# RetroLink.net
KiCad netlist of a schematic drawn in EAGLE
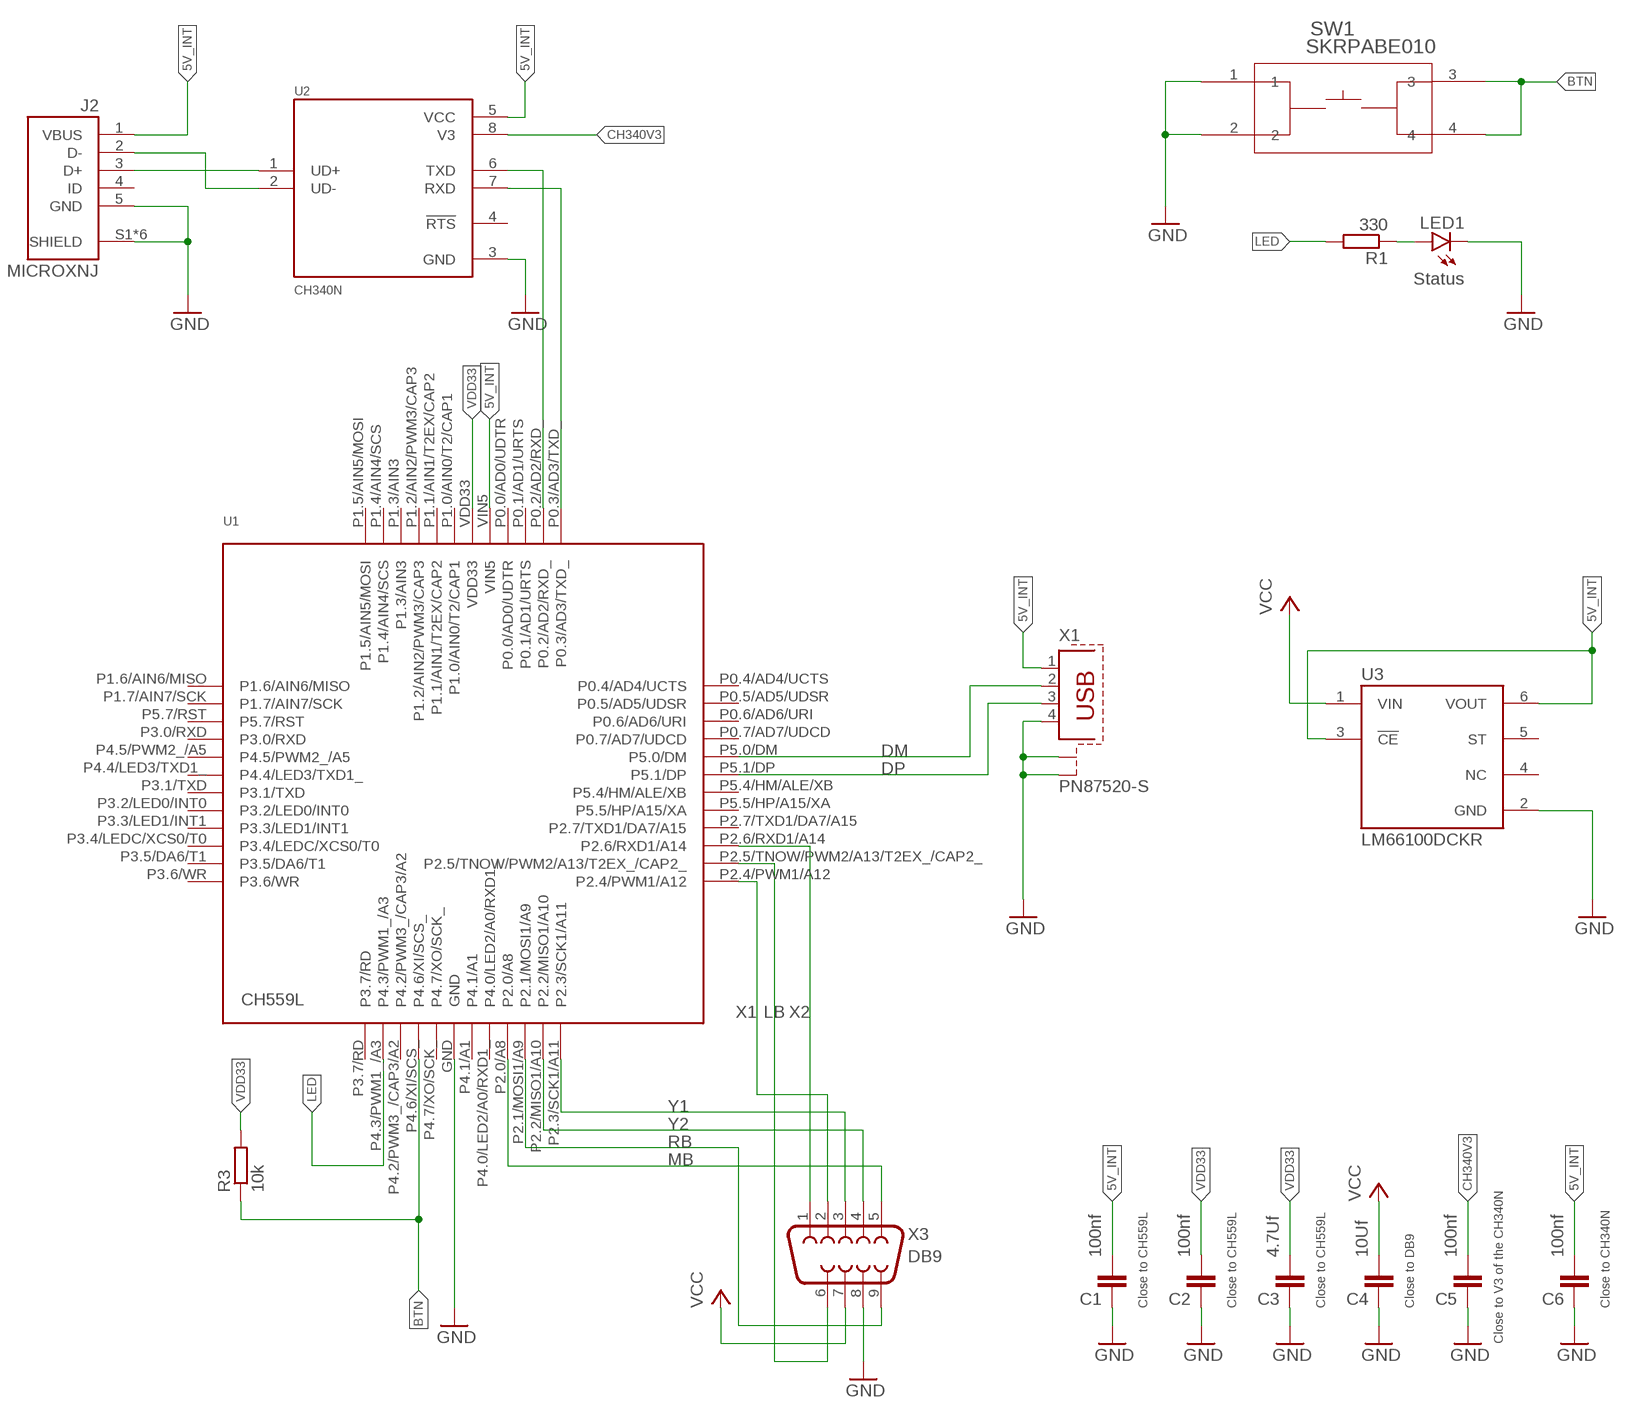
[diagram p0: schematic, sheet 1]

(export (version "E")
  (design (tool "Eeschema 10.0.6"))
  (components
    (comp (ref "C1")
      (value "100nf")
      (footprint "eagle-import:C0603")
      (libsource (lib "eagle-import") (part "C-EUC0603"))
    )
    (comp (ref "C2")
      (value "100nf")
      (footprint "eagle-import:C0603")
      (libsource (lib "eagle-import") (part "C-EUC0603"))
    )
    (comp (ref "C3")
      (value "4.7Uf")
      (footprint "eagle-import:C0603")
      (libsource (lib "eagle-import") (part "C-EUC0603"))
    )
    (comp (ref "C4")
      (value "10Uf")
      (footprint "eagle-import:C0603")
      (libsource (lib "eagle-import") (part "C-EUC0603"))
    )
    (comp (ref "C5")
      (value "100nf")
      (footprint "eagle-import:C0603")
      (libsource (lib "eagle-import") (part "C-EUC0603"))
    )
    (comp (ref "C6")
      (value "100nf")
      (footprint "eagle-import:C0603")
      (libsource (lib "eagle-import") (part "C-EUC0603"))
    )
    (comp (ref "J2")
      (value "MICROXNJ")
      (footprint "eagle-import:SHOUHAN_MICROXNJ")
      (fields (field (name "MF") "Shouhan"))
      (libsource (lib "eagle-import") (part "MICROXNJ"))
    )
    (comp (ref "LED1")
      (value "Status")
      (footprint "eagle-import:SML0603")
      (libsource (lib "eagle-import") (part "LEDSML0603"))
    )
    (comp (ref "R1")
      (value "330")
      (footprint "eagle-import:R0603")
      (libsource (lib "eagle-import") (part "R-EU_R0603"))
    )
    (comp (ref "R3")
      (value "10k")
      (footprint "eagle-import:R0603")
      (libsource (lib "eagle-import") (part "R-EU_R0603"))
    )
    (comp (ref "SW1")
      (value "SKRPABE010")
      (footprint "eagle-import:SW4_SKRPABE010_ALPS")
      (fields (field (name "COPYRIGHT") "Copyright (C) 2026 Ultra Librarian. All rights reserved."))
      (libsource (lib "eagle-import") (part "SKRPABE010"))
    )
    (comp (ref "U1")
      (value "CH559L")
      (footprint "eagle-import:TQFP48_7X7")
      (libsource (lib "eagle-import") (part "CH559L"))
    )
    (comp (ref "U2")
      (value "CH340N")
      (footprint "eagle-import:SOIC127P600X160-8N")
      (fields (field (name "MF") "WCH"))
      (libsource (lib "eagle-import") (part "CH340N"))
    )
    (comp (ref "U3")
      (value "LM66100DCKR")
      (footprint "eagle-import:SOT65P210X110-6N")
      (fields (field (name "MF") "Texas Instruments"))
      (libsource (lib "eagle-import") (part "LM66100DCKR"))
    )
    (comp (ref "X1")
      (value "PN87520-S")
      (footprint "eagle-import:PN87520-S")
      (libsource (lib "eagle-import") (part "PN87520-S"))
    )
    (comp (ref "X3")
      (value "DB9")
      (footprint "eagle-import:F09D")
      (libsource (lib "eagle-import") (part "F09D"))
    )
  )
  (nets
    (net (code "1") (name "/DM") (class "Default")
      (node (ref "U1") (pin "P5.0/DM") (pinfunction "P5.0/DM_P5.0/DM") (pintype "bidirectional"))
      (node (ref "X1") (pin "2") (pinfunction "2_2") (pintype "passive"))
    )
    (net (code "2") (name "/DP") (class "Default")
      (node (ref "U1") (pin "P5.1/DP") (pinfunction "P5.1/DP_P5.1/DP") (pintype "bidirectional"))
      (node (ref "X1") (pin "3") (pinfunction "3_3") (pintype "passive"))
    )
    (net (code "3") (name "/LB") (class "Default")
      (node (ref "U1") (pin "P2.5/TNOW/PWM2/A13/T2EX_/CAP2_") (pinfunction "P2.5/TNOW/PWM2/A13/T2EX_/CAP2__P2.5/TNOW/PWM2/A13/T2EX_/CAP2_") (pintype "bidirectional"))
      (node (ref "X3") (pin "6") (pinfunction "6_6") (pintype "passive"))
    )
    (net (code "4") (name "/MB") (class "Default")
      (node (ref "U1") (pin "P2.0/A8") (pinfunction "P2.0/A8_P2.0/A8") (pintype "bidirectional"))
      (node (ref "X3") (pin "5") (pinfunction "5_5") (pintype "passive"))
    )
    (net (code "5") (name "/RB") (class "Default")
      (node (ref "U1") (pin "P2.1/MOSI1/A9") (pinfunction "P2.1/MOSI1/A9_P2.1/MOSI1/A9") (pintype "bidirectional"))
      (node (ref "X3") (pin "9") (pinfunction "9_9") (pintype "passive"))
    )
    (net (code "6") (name "/X1") (class "Default")
      (node (ref "U1") (pin "P2.4/PWM1/A12") (pinfunction "P2.4/PWM1/A12_P2.4/PWM1/A12") (pintype "bidirectional"))
      (node (ref "X3") (pin "2") (pinfunction "2_2") (pintype "passive"))
    )
    (net (code "7") (name "/X2") (class "Default")
      (node (ref "U1") (pin "P2.6/RXD1/A14") (pinfunction "P2.6/RXD1/A14_P2.6/RXD1/A14") (pintype "bidirectional"))
      (node (ref "X3") (pin "1") (pinfunction "1_1") (pintype "passive"))
    )
    (net (code "8") (name "/Y1") (class "Default")
      (node (ref "U1") (pin "P2.3/SCK1/A11") (pinfunction "P2.3/SCK1/A11_P2.3/SCK1/A11") (pintype "bidirectional"))
      (node (ref "X3") (pin "3") (pinfunction "3_3") (pintype "passive"))
    )
    (net (code "9") (name "/Y2") (class "Default")
      (node (ref "U1") (pin "P2.2/MISO1/A10") (pinfunction "P2.2/MISO1/A10_P2.2/MISO1/A10") (pintype "bidirectional"))
      (node (ref "X3") (pin "4") (pinfunction "4_4") (pintype "passive"))
    )
    (net (code "10") (name "5V_INT") (class "Default")
      (node (ref "C1") (pin "2") (pinfunction "2_2") (pintype "passive"))
      (node (ref "C6") (pin "2") (pinfunction "2_2") (pintype "passive"))
      (node (ref "J2") (pin "1") (pinfunction "VBUS_1") (pintype "power_in"))
      (node (ref "U1") (pin "VIN5") (pinfunction "VIN5_VIN5") (pintype "bidirectional"))
      (node (ref "U2") (pin "5") (pinfunction "VCC_5") (pintype "power_in"))
      (node (ref "U3") (pin "3") (pinfunction "~{CE}_3") (pintype "input"))
      (node (ref "U3") (pin "6") (pinfunction "VOUT_6") (pintype "output"))
      (node (ref "X1") (pin "1") (pinfunction "1_1") (pintype "passive"))
    )
    (net (code "11") (name "BTN") (class "Default")
      (node (ref "R3") (pin "1") (pinfunction "1_1") (pintype "passive"))
      (node (ref "SW1") (pin "3") (pinfunction "3_3") (pintype "passive"))
      (node (ref "SW1") (pin "4") (pinfunction "4_4") (pintype "passive"))
      (node (ref "U1") (pin "P4.6/XI/SCS_") (pinfunction "P4.6/XI/SCS__P4.6/XI/SCS_") (pintype "bidirectional"))
    )
    (net (code "12") (name "CH340V3") (class "Default")
      (node (ref "C5") (pin "2") (pinfunction "2_2") (pintype "passive"))
      (node (ref "U2") (pin "8") (pinfunction "V3_8") (pintype "power_in"))
    )
    (net (code "13") (name "GND") (class "Default")
      (node (ref "C1") (pin "1") (pinfunction "1_1") (pintype "passive"))
      (node (ref "C2") (pin "1") (pinfunction "1_1") (pintype "passive"))
      (node (ref "C3") (pin "1") (pinfunction "1_1") (pintype "passive"))
      (node (ref "C4") (pin "1") (pinfunction "1_1") (pintype "passive"))
      (node (ref "C5") (pin "1") (pinfunction "1_1") (pintype "passive"))
      (node (ref "C6") (pin "1") (pinfunction "1_1") (pintype "passive"))
      (node (ref "J2") (pin "5") (pinfunction "GND_5") (pintype "power_in"))
      (node (ref "J2") (pin "S1") (pinfunction "SHIELD_S1") (pintype "passive"))
      (node (ref "J2") (pin "S2") (pinfunction "SHIELD_S2") (pintype "passive"))
      (node (ref "J2") (pin "S3") (pinfunction "SHIELD_S3") (pintype "passive"))
      (node (ref "J2") (pin "S4") (pinfunction "SHIELD_S4") (pintype "passive"))
      (node (ref "J2") (pin "S5") (pinfunction "SHIELD_S5") (pintype "passive"))
      (node (ref "J2") (pin "S6") (pinfunction "SHIELD_S6") (pintype "passive"))
      (node (ref "LED1") (pin "C") (pinfunction "C_C") (pintype "passive"))
      (node (ref "SW1") (pin "1") (pinfunction "1_1") (pintype "passive"))
      (node (ref "SW1") (pin "2") (pinfunction "2_2") (pintype "passive"))
      (node (ref "U1") (pin "GND") (pinfunction "GND_GND") (pintype "bidirectional"))
      (node (ref "U2") (pin "3") (pinfunction "GND_3") (pintype "power_in"))
      (node (ref "U3") (pin "2") (pinfunction "GND_2") (pintype "power_in"))
      (node (ref "X1") (pin "4") (pinfunction "4_4") (pintype "passive"))
      (node (ref "X1") (pin "S1") (pinfunction "S1_S1") (pintype "passive"))
      (node (ref "X1") (pin "S2") (pinfunction "S2_S2") (pintype "passive"))
      (node (ref "X3") (pin "8") (pinfunction "8_8") (pintype "passive"))
    )
    (net (code "14") (name "LED") (class "Default")
      (node (ref "R1") (pin "2") (pinfunction "2_2") (pintype "passive"))
      (node (ref "U1") (pin "P4.3/PWM1_/A3") (pinfunction "P4.3/PWM1_/A3_P4.3/PWM1_/A3") (pintype "bidirectional"))
    )
    (net (code "15") (name "Net-(J2-D+)") (class "Default")
      (node (ref "J2") (pin "3") (pinfunction "D+_3") (pintype "bidirectional"))
      (node (ref "U2") (pin "1") (pinfunction "UD+_1") (pintype "bidirectional"))
    )
    (net (code "16") (name "Net-(J2-D-)") (class "Default")
      (node (ref "J2") (pin "2") (pinfunction "D-_2") (pintype "bidirectional"))
      (node (ref "U2") (pin "2") (pinfunction "UD-_2") (pintype "bidirectional"))
    )
    (net (code "17") (name "Net-(LED1-PadA)") (class "Default")
      (node (ref "LED1") (pin "A") (pinfunction "A_A") (pintype "passive"))
      (node (ref "R1") (pin "1") (pinfunction "1_1") (pintype "passive"))
    )
    (net (code "18") (name "Net-(U2-RXD)") (class "Default")
      (node (ref "U1") (pin "P0.3/AD3/TXD_") (pinfunction "P0.3/AD3/TXD__P0.3/AD3/TXD_") (pintype "bidirectional"))
      (node (ref "U2") (pin "7") (pinfunction "RXD_7") (pintype "input"))
    )
    (net (code "19") (name "Net-(U2-TXD)") (class "Default")
      (node (ref "U1") (pin "P0.2/AD2/RXD_") (pinfunction "P0.2/AD2/RXD__P0.2/AD2/RXD_") (pintype "bidirectional"))
      (node (ref "U2") (pin "6") (pinfunction "TXD_6") (pintype "output"))
    )
    (net (code "20") (name "VCC") (class "Default")
      (node (ref "C4") (pin "2") (pinfunction "2_2") (pintype "passive"))
      (node (ref "U3") (pin "1") (pinfunction "VIN_1") (pintype "input"))
      (node (ref "X3") (pin "7") (pinfunction "7_7") (pintype "passive"))
    )
    (net (code "21") (name "VDD33") (class "Default")
      (node (ref "C2") (pin "2") (pinfunction "2_2") (pintype "passive"))
      (node (ref "C3") (pin "2") (pinfunction "2_2") (pintype "passive"))
      (node (ref "R3") (pin "2") (pinfunction "2_2") (pintype "passive"))
      (node (ref "U1") (pin "VDD33") (pinfunction "VDD33_VDD33") (pintype "bidirectional"))
    )
    (net (code "22") (name "unconnected-(J2-ID-Pad4)") (class "Default")
      (node (ref "J2") (pin "4") (pinfunction "ID_4") (pintype "bidirectional"))
    )
    (net (code "23") (name "unconnected-(U1-PadP0.0{slash}AD0{slash}UDTR)") (class "Default")
      (node (ref "U1") (pin "P0.0/AD0/UDTR") (pinfunction "P0.0/AD0/UDTR_P0.0/AD0/UDTR") (pintype "bidirectional"))
    )
    (net (code "24") (name "unconnected-(U1-PadP0.1{slash}AD1{slash}URTS)") (class "Default")
      (node (ref "U1") (pin "P0.1/AD1/URTS") (pinfunction "P0.1/AD1/URTS_P0.1/AD1/URTS") (pintype "bidirectional"))
    )
    (net (code "25") (name "unconnected-(U1-PadP0.4{slash}AD4{slash}UCTS)") (class "Default")
      (node (ref "U1") (pin "P0.4/AD4/UCTS") (pinfunction "P0.4/AD4/UCTS_P0.4/AD4/UCTS") (pintype "bidirectional"))
    )
    (net (code "26") (name "unconnected-(U1-PadP0.5{slash}AD5{slash}UDSR)") (class "Default")
      (node (ref "U1") (pin "P0.5/AD5/UDSR") (pinfunction "P0.5/AD5/UDSR_P0.5/AD5/UDSR") (pintype "bidirectional"))
    )
    (net (code "27") (name "unconnected-(U1-PadP0.6{slash}AD6{slash}URI)") (class "Default")
      (node (ref "U1") (pin "P0.6/AD6/URI") (pinfunction "P0.6/AD6/URI_P0.6/AD6/URI") (pintype "bidirectional"))
    )
    (net (code "28") (name "unconnected-(U1-PadP0.7{slash}AD7{slash}UDCD)") (class "Default")
      (node (ref "U1") (pin "P0.7/AD7/UDCD") (pinfunction "P0.7/AD7/UDCD_P0.7/AD7/UDCD") (pintype "bidirectional"))
    )
    (net (code "29") (name "unconnected-(U1-PadP1.0{slash}AIN0{slash}T2{slash}CAP1)") (class "Default")
      (node (ref "U1") (pin "P1.0/AIN0/T2/CAP1") (pinfunction "P1.0/AIN0/T2/CAP1_P1.0/AIN0/T2/CAP1") (pintype "bidirectional"))
    )
    (net (code "30") (name "unconnected-(U1-PadP1.1{slash}AIN1{slash}T2EX{slash}CAP2)") (class "Default")
      (node (ref "U1") (pin "P1.1/AIN1/T2EX/CAP2") (pinfunction "P1.1/AIN1/T2EX/CAP2_P1.1/AIN1/T2EX/CAP2") (pintype "bidirectional"))
    )
    (net (code "31") (name "unconnected-(U1-PadP1.2{slash}AIN2{slash}PWM3{slash}CAP3)") (class "Default")
      (node (ref "U1") (pin "P1.2/AIN2/PWM3/CAP3") (pinfunction "P1.2/AIN2/PWM3/CAP3_P1.2/AIN2/PWM3/CAP3") (pintype "bidirectional"))
    )
    (net (code "32") (name "unconnected-(U1-PadP1.3{slash}AIN3)") (class "Default")
      (node (ref "U1") (pin "P1.3/AIN3") (pinfunction "P1.3/AIN3_P1.3/AIN3") (pintype "bidirectional"))
    )
    (net (code "33") (name "unconnected-(U1-PadP1.4{slash}AIN4{slash}SCS)") (class "Default")
      (node (ref "U1") (pin "P1.4/AIN4/SCS") (pinfunction "P1.4/AIN4/SCS_P1.4/AIN4/SCS") (pintype "bidirectional"))
    )
    (net (code "34") (name "unconnected-(U1-PadP1.5{slash}AIN5{slash}MOSI)") (class "Default")
      (node (ref "U1") (pin "P1.5/AIN5/MOSI") (pinfunction "P1.5/AIN5/MOSI_P1.5/AIN5/MOSI") (pintype "bidirectional"))
    )
    (net (code "35") (name "unconnected-(U1-PadP1.6{slash}AIN6{slash}MISO)") (class "Default")
      (node (ref "U1") (pin "P1.6/AIN6/MISO") (pinfunction "P1.6/AIN6/MISO_P1.6/AIN6/MISO") (pintype "bidirectional"))
    )
    (net (code "36") (name "unconnected-(U1-PadP1.7{slash}AIN7{slash}SCK)") (class "Default")
      (node (ref "U1") (pin "P1.7/AIN7/SCK") (pinfunction "P1.7/AIN7/SCK_P1.7/AIN7/SCK") (pintype "bidirectional"))
    )
    (net (code "37") (name "unconnected-(U1-PadP2.7{slash}TXD1{slash}DA7{slash}A15)") (class "Default")
      (node (ref "U1") (pin "P2.7/TXD1/DA7/A15") (pinfunction "P2.7/TXD1/DA7/A15_P2.7/TXD1/DA7/A15") (pintype "bidirectional"))
    )
    (net (code "38") (name "unconnected-(U1-PadP3.0{slash}RXD)") (class "Default")
      (node (ref "U1") (pin "P3.0/RXD") (pinfunction "P3.0/RXD_P3.0/RXD") (pintype "bidirectional"))
    )
    (net (code "39") (name "unconnected-(U1-PadP3.1{slash}TXD)") (class "Default")
      (node (ref "U1") (pin "P3.1/TXD") (pinfunction "P3.1/TXD_P3.1/TXD") (pintype "bidirectional"))
    )
    (net (code "40") (name "unconnected-(U1-PadP3.2{slash}LED0{slash}INT0)") (class "Default")
      (node (ref "U1") (pin "P3.2/LED0/INT0") (pinfunction "P3.2/LED0/INT0_P3.2/LED0/INT0") (pintype "bidirectional"))
    )
    (net (code "41") (name "unconnected-(U1-PadP3.3{slash}LED1{slash}INT1)") (class "Default")
      (node (ref "U1") (pin "P3.3/LED1/INT1") (pinfunction "P3.3/LED1/INT1_P3.3/LED1/INT1") (pintype "bidirectional"))
    )
    (net (code "42") (name "unconnected-(U1-PadP3.4{slash}LEDC{slash}XCS0{slash}T0)") (class "Default")
      (node (ref "U1") (pin "P3.4/LEDC/XCS0/T0") (pinfunction "P3.4/LEDC/XCS0/T0_P3.4/LEDC/XCS0/T0") (pintype "bidirectional"))
    )
    (net (code "43") (name "unconnected-(U1-PadP3.5{slash}DA6{slash}T1)") (class "Default")
      (node (ref "U1") (pin "P3.5/DA6/T1") (pinfunction "P3.5/DA6/T1_P3.5/DA6/T1") (pintype "bidirectional"))
    )
    (net (code "44") (name "unconnected-(U1-PadP3.6{slash}WR)") (class "Default")
      (node (ref "U1") (pin "P3.6/WR") (pinfunction "P3.6/WR_P3.6/WR") (pintype "bidirectional"))
    )
    (net (code "45") (name "unconnected-(U1-PadP3.7{slash}RD)") (class "Default")
      (node (ref "U1") (pin "P3.7/RD") (pinfunction "P3.7/RD_P3.7/RD") (pintype "bidirectional"))
    )
    (net (code "46") (name "unconnected-(U1-PadP4.0{slash}LED2{slash}A0{slash}RXD1_)") (class "Default")
      (node (ref "U1") (pin "P4.0/LED2/A0/RXD1_") (pinfunction "P4.0/LED2/A0/RXD1__P4.0/LED2/A0/RXD1_") (pintype "bidirectional"))
    )
    (net (code "47") (name "unconnected-(U1-PadP4.1{slash}A1)") (class "Default")
      (node (ref "U1") (pin "P4.1/A1") (pinfunction "P4.1/A1_P4.1/A1") (pintype "bidirectional"))
    )
    (net (code "48") (name "unconnected-(U1-PadP4.2{slash}PWM3_{slash}CAP3{slash}A2)") (class "Default")
      (node (ref "U1") (pin "P4.2/PWM3_/CAP3/A2") (pinfunction "P4.2/PWM3_/CAP3/A2_P4.2/PWM3_/CAP3/A2") (pintype "bidirectional"))
    )
    (net (code "49") (name "unconnected-(U1-PadP4.4{slash}LED3{slash}TXD1_)") (class "Default")
      (node (ref "U1") (pin "P4.4/LED3/TXD1_") (pinfunction "P4.4/LED3/TXD1__P4.4/LED3/TXD1_") (pintype "bidirectional"))
    )
    (net (code "50") (name "unconnected-(U1-PadP4.5{slash}PWM2_{slash}A5)") (class "Default")
      (node (ref "U1") (pin "P4.5/PWM2_/A5") (pinfunction "P4.5/PWM2_/A5_P4.5/PWM2_/A5") (pintype "bidirectional"))
    )
    (net (code "51") (name "unconnected-(U1-PadP4.7{slash}XO{slash}SCK_)") (class "Default")
      (node (ref "U1") (pin "P4.7/XO/SCK_") (pinfunction "P4.7/XO/SCK__P4.7/XO/SCK_") (pintype "bidirectional"))
    )
    (net (code "52") (name "unconnected-(U1-PadP5.4{slash}HM{slash}ALE{slash}XB)") (class "Default")
      (node (ref "U1") (pin "P5.4/HM/ALE/XB") (pinfunction "P5.4/HM/ALE/XB_P5.4/HM/ALE/XB") (pintype "bidirectional"))
    )
    (net (code "53") (name "unconnected-(U1-PadP5.5{slash}HP{slash}A15{slash}XA)") (class "Default")
      (node (ref "U1") (pin "P5.5/HP/A15/XA") (pinfunction "P5.5/HP/A15/XA_P5.5/HP/A15/XA") (pintype "bidirectional"))
    )
    (net (code "54") (name "unconnected-(U1-PadP5.7{slash}RST)") (class "Default")
      (node (ref "U1") (pin "P5.7/RST") (pinfunction "P5.7/RST_P5.7/RST") (pintype "bidirectional"))
    )
    (net (code "55") (name "unconnected-(U2-~{RTS}-Pad4)") (class "Default")
      (node (ref "U2") (pin "4") (pinfunction "~{RTS}_4") (pintype "output"))
    )
    (net (code "56") (name "unconnected-(U3-NC-Pad4)") (class "Default")
      (node (ref "U3") (pin "4") (pinfunction "NC_4") (pintype "no_connect"))
    )
    (net (code "57") (name "unconnected-(U3-ST-Pad5)") (class "Default")
      (node (ref "U3") (pin "5") (pinfunction "ST_5") (pintype "output"))
    )
  )
)
